# Smartboot_Prototype_version_4.net
KiCad netlist of a schematic drawn in EAGLE
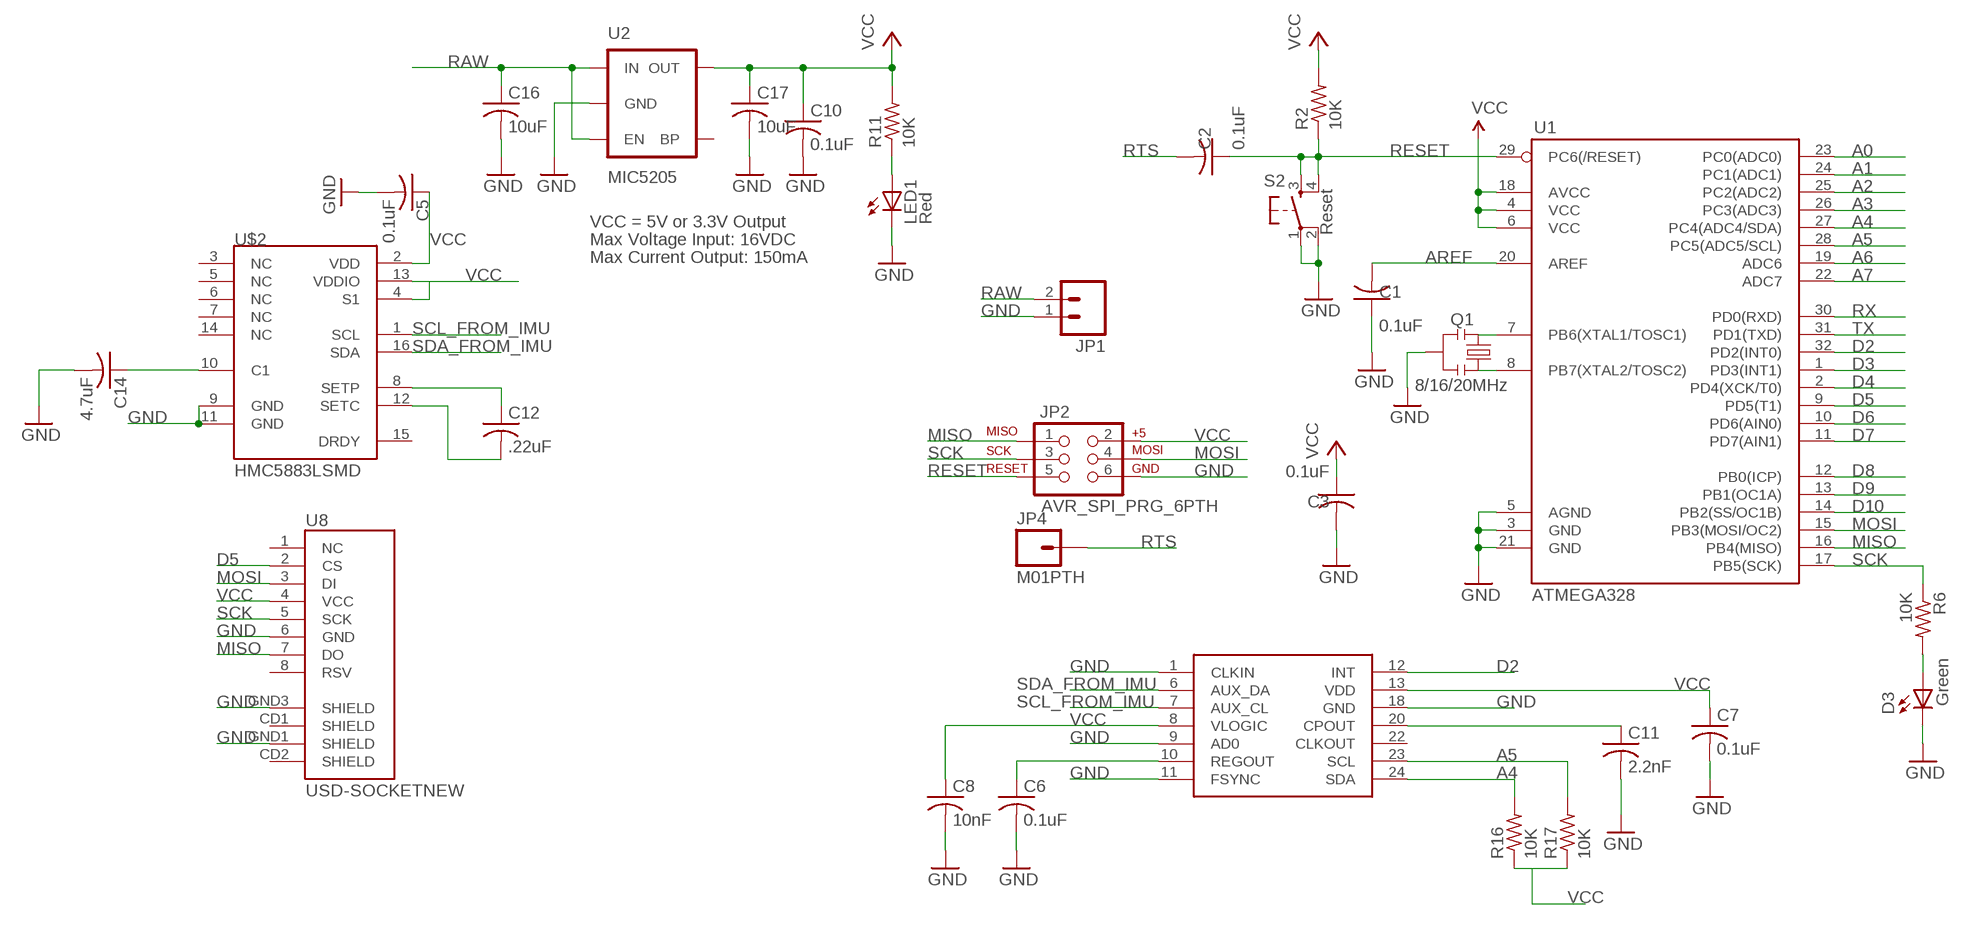
[diagram p0: schematic, sheet 1]
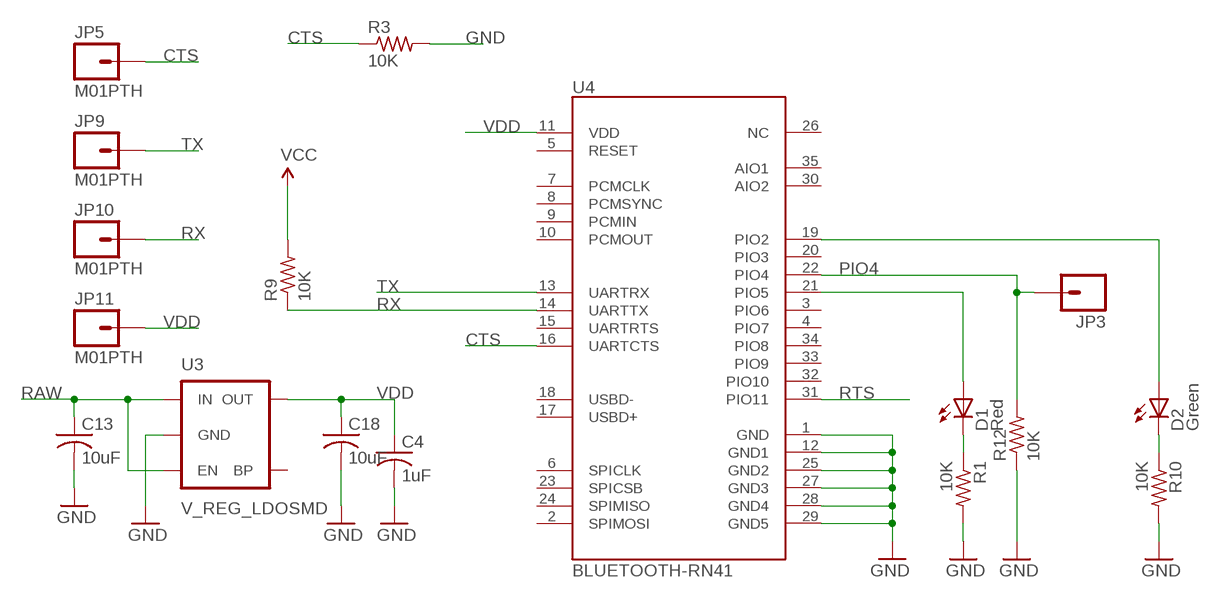
[diagram p1: schematic, sheet 2]

(export (version "E")
  (design (tool "Eeschema 10.0.6"))
  (components
    (comp (ref "C4")
      (value "1uF")
      (footprint "eagle-import:C0603")
      (libsource (lib "eagle-import") (part "C-USC0603"))
    )
    (comp (ref "C13")
      (value "10uF")
      (footprint "eagle-import:C0603")
      (libsource (lib "eagle-import") (part "C-USC0603"))
    )
    (comp (ref "C18")
      (value "10uF")
      (footprint "eagle-import:C0603")
      (libsource (lib "eagle-import") (part "C-USC0603"))
    )
    (comp (ref "D1")
      (value "Red")
      (footprint "eagle-import:LED-0603")
      (libsource (lib "eagle-import") (part "LED0603"))
    )
    (comp (ref "D2")
      (value "Green")
      (footprint "eagle-import:LED-0603")
      (libsource (lib "eagle-import") (part "LED0603"))
    )
    (comp (ref "JP3")
      (value "M01SMDNS")
      (footprint "eagle-import:1X01NS")
      (libsource (lib "eagle-import") (part "M01SMDNS"))
    )
    (comp (ref "JP5")
      (value "M01PTH")
      (footprint "eagle-import:1X01")
      (libsource (lib "eagle-import") (part "SparkFun-Connectors_M01PTH"))
    )
    (comp (ref "JP9")
      (value "M01PTH")
      (footprint "eagle-import:1X01")
      (libsource (lib "eagle-import") (part "SparkFun-Connectors_M01PTH"))
    )
    (comp (ref "JP10")
      (value "M01PTH")
      (footprint "eagle-import:1X01")
      (libsource (lib "eagle-import") (part "SparkFun-Connectors_M01PTH"))
    )
    (comp (ref "JP11")
      (value "M01PTH")
      (footprint "eagle-import:1X01")
      (libsource (lib "eagle-import") (part "SparkFun-Connectors_M01PTH"))
    )
    (comp (ref "R1")
      (value "10K")
      (footprint "eagle-import:R0603")
      (libsource (lib "eagle-import") (part "R-US_R0603"))
    )
    (comp (ref "R3")
      (value "10K")
      (footprint "eagle-import:R0603")
      (libsource (lib "eagle-import") (part "R-US_R0603"))
    )
    (comp (ref "R9")
      (value "10K")
      (footprint "eagle-import:R0603")
      (libsource (lib "eagle-import") (part "R-US_R0603"))
    )
    (comp (ref "R10")
      (value "10K")
      (footprint "eagle-import:R0603")
      (libsource (lib "eagle-import") (part "R-US_R0603"))
    )
    (comp (ref "R12")
      (value "10K")
      (footprint "eagle-import:R0603")
      (libsource (lib "eagle-import") (part "R-US_R0603"))
    )
    (comp (ref "U3")
      (value "V_REG_LDOSMD")
      (footprint "eagle-import:SOT23-5")
      (libsource (lib "eagle-import") (part "V_REG_LDOSMD"))
    )
    (comp (ref "U4")
      (value "BLUETOOTH-RN41")
      (footprint "eagle-import:RN41")
      (libsource (lib "eagle-import") (part "BLUETOOTH-RN41{dblquote}"))
    )
    (comp (ref "C1")
      (value "0.1uF")
      (footprint "eagle-import:C0603")
      (libsource (lib "eagle-import") (part "C-USC0603"))
    )
    (comp (ref "C2")
      (value "0.1uF")
      (footprint "eagle-import:C0603")
      (libsource (lib "eagle-import") (part "C-USC0603"))
    )
    (comp (ref "C3")
      (value "0.1uF")
      (footprint "eagle-import:C0603")
      (libsource (lib "eagle-import") (part "C-USC0603"))
    )
    (comp (ref "C5")
      (value "0.1uF")
      (footprint "eagle-import:C0603")
      (libsource (lib "eagle-import") (part "C-USC0603"))
    )
    (comp (ref "C6")
      (value "0.1uF")
      (footprint "eagle-import:C0603")
      (libsource (lib "eagle-import") (part "C-USC0603"))
    )
    (comp (ref "C7")
      (value "0.1uF")
      (footprint "eagle-import:C0603")
      (libsource (lib "eagle-import") (part "C-USC0603"))
    )
    (comp (ref "C8")
      (value "10nF")
      (footprint "eagle-import:C0603")
      (libsource (lib "eagle-import") (part "C-USC0603"))
    )
    (comp (ref "C10")
      (value "0.1uF")
      (footprint "eagle-import:C0603")
      (libsource (lib "eagle-import") (part "C-USC0603"))
    )
    (comp (ref "C11")
      (value "2.2nF")
      (footprint "eagle-import:C0603")
      (libsource (lib "eagle-import") (part "C-USC0603"))
    )
    (comp (ref "C12")
      (value ".22uF")
      (footprint "eagle-import:C0603")
      (libsource (lib "eagle-import") (part "C-USC0603"))
    )
    (comp (ref "C14")
      (value "4.7uF")
      (footprint "eagle-import:C0603")
      (libsource (lib "eagle-import") (part "C-USC0603"))
    )
    (comp (ref "C16")
      (value "10uF")
      (footprint "eagle-import:C0603")
      (libsource (lib "eagle-import") (part "C-USC0603"))
    )
    (comp (ref "C17")
      (value "10uF")
      (footprint "eagle-import:C0603")
      (libsource (lib "eagle-import") (part "C-USC0603"))
    )
    (comp (ref "D3")
      (value "Green")
      (footprint "eagle-import:LED-0603")
      (libsource (lib "eagle-import") (part "LED0603"))
    )
    (comp (ref "JP1")
      (value "M02-JST-2MM-SMT")
      (footprint "eagle-import:JST-2-SMD")
      (libsource (lib "eagle-import") (part "M02-JST-2MM-SMT"))
    )
    (comp (ref "JP2")
      (value "AVR_SPI_PRG_6PTH")
      (footprint "eagle-import:2X3")
      (libsource (lib "eagle-import") (part "AVR_SPI_PRG_6PTH"))
    )
    (comp (ref "JP4")
      (value "M01PTH")
      (footprint "eagle-import:1X01")
      (libsource (lib "eagle-import") (part "SparkFun-Connectors_M01PTH"))
    )
    (comp (ref "LED1")
      (value "Red")
      (footprint "eagle-import:LED-0603")
      (libsource (lib "eagle-import") (part "LED0603"))
    )
    (comp (ref "Q1")
      (value "8/16/20MHz")
      (footprint "eagle-import:RESONATOR-SMD")
      (libsource (lib "eagle-import") (part "RESONATORSMD"))
    )
    (comp (ref "R2")
      (value "10K")
      (footprint "eagle-import:R0603")
      (libsource (lib "eagle-import") (part "R-US_R0603"))
    )
    (comp (ref "R6")
      (value "10K")
      (footprint "eagle-import:R0603")
      (libsource (lib "eagle-import") (part "R-US_R0603"))
    )
    (comp (ref "R11")
      (value "10K")
      (footprint "eagle-import:R0603")
      (libsource (lib "eagle-import") (part "R-US_R0603"))
    )
    (comp (ref "R16")
      (value "10K")
      (footprint "eagle-import:R0603")
      (libsource (lib "eagle-import") (part "R-US_R0603"))
    )
    (comp (ref "R17")
      (value "10K")
      (footprint "eagle-import:R0603")
      (libsource (lib "eagle-import") (part "R-US_R0603"))
    )
    (comp (ref "S2")
      (value "Reset")
      (footprint "eagle-import:TACTILE_SWITCH_SMD")
      (libsource (lib "eagle-import") (part "TAC_SWITCHSMD"))
    )
    (comp (ref "U$2")
      (value "HMC5883LSMD")
      (footprint "eagle-import:16LPCC")
      (libsource (lib "eagle-import") (part "HMC5883LSMD"))
    )
    (comp (ref "U$5")
      (value "MPU-6050A")
      (footprint "eagle-import:QFN-24-NP")
      (libsource (lib "eagle-import") (part "MPU-6050A"))
    )
    (comp (ref "U1")
      (value "ATMEGA328")
      (footprint "eagle-import:TQFP32-08")
      (libsource (lib "eagle-import") (part "ATMEGA168"))
    )
    (comp (ref "U2")
      (value "MIC5205")
      (footprint "eagle-import:SOT23-5")
      (libsource (lib "eagle-import") (part "V_REG_LDOSMD"))
    )
    (comp (ref "U8")
      (value "USD-SOCKETNEW")
      (footprint "eagle-import:MICRO-SD-SOCKET-PP")
      (libsource (lib "eagle-import") (part "USD-SOCKETNEW"))
    )
  )
  (nets
    (net (code "1") (name "A0") (class "Default")
      (node (ref "U1") (pin "23") (pinfunction "PC0(ADC0)_23") (pintype "bidirectional"))
    )
    (net (code "2") (name "A1") (class "Default")
      (node (ref "U1") (pin "24") (pinfunction "PC1(ADC1)_24") (pintype "bidirectional"))
    )
    (net (code "3") (name "A2") (class "Default")
      (node (ref "U1") (pin "25") (pinfunction "PC2(ADC2)_25") (pintype "bidirectional"))
    )
    (net (code "4") (name "A3") (class "Default")
      (node (ref "U1") (pin "26") (pinfunction "PC3(ADC3)_26") (pintype "bidirectional"))
    )
    (net (code "5") (name "A4") (class "Default")
      (node (ref "R16") (pin "2") (pinfunction "2_2") (pintype "passive"))
      (node (ref "U$5") (pin "24") (pinfunction "SDA_24") (pintype "bidirectional"))
      (node (ref "U1") (pin "27") (pinfunction "PC4(ADC4/SDA)_27") (pintype "bidirectional"))
    )
    (net (code "6") (name "A5") (class "Default")
      (node (ref "R17") (pin "2") (pinfunction "2_2") (pintype "passive"))
      (node (ref "U$5") (pin "23") (pinfunction "SCL_23") (pintype "bidirectional"))
      (node (ref "U1") (pin "28") (pinfunction "PC5(ADC5/SCL)_28") (pintype "bidirectional"))
    )
    (net (code "7") (name "A6") (class "Default")
      (node (ref "U1") (pin "19") (pinfunction "ADC6_19") (pintype "bidirectional"))
    )
    (net (code "8") (name "A7") (class "Default")
      (node (ref "U1") (pin "22") (pinfunction "ADC7_22") (pintype "bidirectional"))
    )
    (net (code "9") (name "AREF") (class "Default")
      (node (ref "C1") (pin "2") (pinfunction "2_2") (pintype "passive"))
      (node (ref "U1") (pin "20") (pinfunction "AREF_20") (pintype "bidirectional"))
    )
    (net (code "10") (name "CTS") (class "Default")
      (node (ref "JP5") (pin "1") (pinfunction "1_1") (pintype "passive"))
      (node (ref "R3") (pin "1") (pinfunction "1_1") (pintype "passive"))
      (node (ref "U4") (pin "16") (pinfunction "UARTCTS_16") (pintype "bidirectional"))
    )
    (net (code "11") (name "D2") (class "Default")
      (node (ref "U$5") (pin "12") (pinfunction "INT_12") (pintype "bidirectional"))
      (node (ref "U1") (pin "32") (pinfunction "PD2(INT0)_32") (pintype "bidirectional"))
    )
    (net (code "12") (name "D3") (class "Default")
      (node (ref "U1") (pin "1") (pinfunction "PD3(INT1)_1") (pintype "bidirectional"))
    )
    (net (code "13") (name "D4") (class "Default")
      (node (ref "U1") (pin "2") (pinfunction "PD4(XCK/T0)_2") (pintype "bidirectional"))
    )
    (net (code "14") (name "D5") (class "Default")
      (node (ref "U1") (pin "9") (pinfunction "PD5(T1)_9") (pintype "bidirectional"))
      (node (ref "U8") (pin "2") (pinfunction "CS_2") (pintype "bidirectional"))
    )
    (net (code "15") (name "D6") (class "Default")
      (node (ref "U1") (pin "10") (pinfunction "PD6(AIN0)_10") (pintype "bidirectional"))
    )
    (net (code "16") (name "D7") (class "Default")
      (node (ref "U1") (pin "11") (pinfunction "PD7(AIN1)_11") (pintype "bidirectional"))
    )
    (net (code "17") (name "D8") (class "Default")
      (node (ref "U1") (pin "12") (pinfunction "PB0(ICP)_12") (pintype "bidirectional"))
    )
    (net (code "18") (name "D9") (class "Default")
      (node (ref "U1") (pin "13") (pinfunction "PB1(OC1A)_13") (pintype "bidirectional"))
    )
    (net (code "19") (name "D10") (class "Default")
      (node (ref "U1") (pin "14") (pinfunction "PB2(SS/OC1B)_14") (pintype "bidirectional"))
    )
    (net (code "20") (name "GND") (class "Default")
      (node (ref "C1") (pin "1") (pinfunction "1_1") (pintype "passive"))
      (node (ref "C10") (pin "2") (pinfunction "2_2") (pintype "passive"))
      (node (ref "C11") (pin "2") (pinfunction "2_2") (pintype "passive"))
      (node (ref "C13") (pin "2") (pinfunction "2_2") (pintype "passive"))
      (node (ref "C14") (pin "2") (pinfunction "2_2") (pintype "passive"))
      (node (ref "C16") (pin "2") (pinfunction "2_2") (pintype "passive"))
      (node (ref "C17") (pin "2") (pinfunction "2_2") (pintype "passive"))
      (node (ref "C18") (pin "2") (pinfunction "2_2") (pintype "passive"))
      (node (ref "C3") (pin "2") (pinfunction "2_2") (pintype "passive"))
      (node (ref "C4") (pin "2") (pinfunction "2_2") (pintype "passive"))
      (node (ref "C5") (pin "2") (pinfunction "2_2") (pintype "passive"))
      (node (ref "C6") (pin "2") (pinfunction "2_2") (pintype "passive"))
      (node (ref "C7") (pin "2") (pinfunction "2_2") (pintype "passive"))
      (node (ref "C8") (pin "2") (pinfunction "2_2") (pintype "passive"))
      (node (ref "D3") (pin "C") (pinfunction "C_C") (pintype "passive"))
      (node (ref "JP1") (pin "1") (pinfunction "2_1") (pintype "passive"))
      (node (ref "JP2") (pin "6") (pinfunction "6_6") (pintype "passive"))
      (node (ref "LED1") (pin "C") (pinfunction "C_C") (pintype "passive"))
      (node (ref "Q1") (pin "2") (pinfunction "2_2") (pintype "passive"))
      (node (ref "R1") (pin "2") (pinfunction "2_2") (pintype "passive"))
      (node (ref "R10") (pin "2") (pinfunction "2_2") (pintype "passive"))
      (node (ref "R12") (pin "1") (pinfunction "1_1") (pintype "passive"))
      (node (ref "R3") (pin "2") (pinfunction "2_2") (pintype "passive"))
      (node (ref "S2") (pin "1") (pinfunction "1_1") (pintype "passive"))
      (node (ref "S2") (pin "2") (pinfunction "2_2") (pintype "passive"))
      (node (ref "U$2") (pin "11") (pinfunction "GND_11") (pintype "bidirectional"))
      (node (ref "U$2") (pin "9") (pinfunction "GND_9") (pintype "bidirectional"))
      (node (ref "U$5") (pin "1") (pinfunction "CLKIN_1") (pintype "bidirectional"))
      (node (ref "U$5") (pin "11") (pinfunction "FSYNC_11") (pintype "bidirectional"))
      (node (ref "U$5") (pin "18") (pinfunction "GND_18") (pintype "bidirectional"))
      (node (ref "U$5") (pin "9") (pinfunction "AD0_9") (pintype "bidirectional"))
      (node (ref "U1") (pin "21") (pinfunction "GND_21") (pintype "bidirectional"))
      (node (ref "U1") (pin "3") (pinfunction "GND_3") (pintype "bidirectional"))
      (node (ref "U1") (pin "5") (pinfunction "AGND_5") (pintype "bidirectional"))
      (node (ref "U2") (pin "2") (pinfunction "GND_2") (pintype "input"))
      (node (ref "U3") (pin "2") (pinfunction "GND_2") (pintype "input"))
      (node (ref "U4") (pin "1") (pinfunction "GND_1") (pintype "bidirectional"))
      (node (ref "U4") (pin "12") (pinfunction "GND1_12") (pintype "bidirectional"))
      (node (ref "U4") (pin "25") (pinfunction "GND2_25") (pintype "bidirectional"))
      (node (ref "U4") (pin "27") (pinfunction "GND3_27") (pintype "bidirectional"))
      (node (ref "U4") (pin "28") (pinfunction "GND4_28") (pintype "bidirectional"))
      (node (ref "U4") (pin "29") (pinfunction "GND5_29") (pintype "bidirectional"))
      (node (ref "U8") (pin "6") (pinfunction "GND_6") (pintype "bidirectional"))
      (node (ref "U8") (pin "GND1") (pinfunction "SHIELD_GND1") (pintype "bidirectional"))
      (node (ref "U8") (pin "GND3") (pinfunction "SHIELD_GND3") (pintype "bidirectional"))
    )
    (net (code "21") (name "MISO") (class "Default")
      (node (ref "JP2") (pin "1") (pinfunction "1_1") (pintype "passive"))
      (node (ref "U1") (pin "16") (pinfunction "PB4(MISO)_16") (pintype "bidirectional"))
      (node (ref "U8") (pin "7") (pinfunction "DO_7") (pintype "bidirectional"))
    )
    (net (code "22") (name "MOSI") (class "Default")
      (node (ref "JP2") (pin "4") (pinfunction "4_4") (pintype "passive"))
      (node (ref "U1") (pin "15") (pinfunction "PB3(MOSI/OC2)_15") (pintype "bidirectional"))
      (node (ref "U8") (pin "3") (pinfunction "DI_3") (pintype "bidirectional"))
    )
    (net (code "23") (name "Net-(D1-PadC)") (class "Default")
      (node (ref "D1") (pin "C") (pinfunction "C_C") (pintype "passive"))
      (node (ref "R1") (pin "1") (pinfunction "1_1") (pintype "passive"))
    )
    (net (code "24") (name "Net-(D2-PadC)") (class "Default")
      (node (ref "D2") (pin "C") (pinfunction "C_C") (pintype "passive"))
      (node (ref "R10") (pin "1") (pinfunction "1_1") (pintype "passive"))
    )
    (net (code "25") (name "Net-(D3-PadA)") (class "Default")
      (node (ref "D3") (pin "A") (pinfunction "A_A") (pintype "passive"))
      (node (ref "R6") (pin "2") (pinfunction "2_2") (pintype "passive"))
    )
    (net (code "26") (name "Net-(LED1-PadA)") (class "Default")
      (node (ref "LED1") (pin "A") (pinfunction "A_A") (pintype "passive"))
      (node (ref "R11") (pin "1") (pinfunction "1_1") (pintype "passive"))
    )
    (net (code "27") (name "Net-(U$2-C1)") (class "Default")
      (node (ref "C14") (pin "1") (pinfunction "1_1") (pintype "passive"))
      (node (ref "U$2") (pin "10") (pinfunction "C1_10") (pintype "bidirectional"))
    )
    (net (code "28") (name "Net-(U$2-SETC)") (class "Default")
      (node (ref "C12") (pin "2") (pinfunction "2_2") (pintype "passive"))
      (node (ref "U$2") (pin "12") (pinfunction "SETC_12") (pintype "bidirectional"))
    )
    (net (code "29") (name "Net-(U$2-SETP)") (class "Default")
      (node (ref "C12") (pin "1") (pinfunction "1_1") (pintype "passive"))
      (node (ref "U$2") (pin "8") (pinfunction "SETP_8") (pintype "bidirectional"))
    )
    (net (code "30") (name "Net-(U$5-CPOUT)") (class "Default")
      (node (ref "C11") (pin "1") (pinfunction "1_1") (pintype "passive"))
      (node (ref "U$5") (pin "20") (pinfunction "CPOUT_20") (pintype "bidirectional"))
    )
    (net (code "31") (name "Net-(U$5-REGOUT)") (class "Default")
      (node (ref "C6") (pin "1") (pinfunction "1_1") (pintype "passive"))
      (node (ref "U$5") (pin "10") (pinfunction "REGOUT_10") (pintype "bidirectional"))
    )
    (net (code "32") (name "Net-(U1-PB6(XTAL1{slash}TOSC1))") (class "Default")
      (node (ref "Q1") (pin "3") (pinfunction "3_3") (pintype "passive"))
      (node (ref "U1") (pin "7") (pinfunction "PB6(XTAL1/TOSC1)_7") (pintype "bidirectional"))
    )
    (net (code "33") (name "Net-(U1-PB7(XTAL2{slash}TOSC2))") (class "Default")
      (node (ref "Q1") (pin "1") (pinfunction "1_1") (pintype "passive"))
      (node (ref "U1") (pin "8") (pinfunction "PB7(XTAL2/TOSC2)_8") (pintype "bidirectional"))
    )
    (net (code "34") (name "Net-(U4-PIO2)") (class "Default")
      (node (ref "D2") (pin "A") (pinfunction "A_A") (pintype "passive"))
      (node (ref "U4") (pin "19") (pinfunction "PIO2_19") (pintype "bidirectional"))
    )
    (net (code "35") (name "Net-(U4-PIO5)") (class "Default")
      (node (ref "D1") (pin "A") (pinfunction "A_A") (pintype "passive"))
      (node (ref "U4") (pin "21") (pinfunction "PIO5_21") (pintype "bidirectional"))
    )
    (net (code "36") (name "PIO4") (class "Default")
      (node (ref "JP3") (pin "1") (pinfunction "1_1") (pintype "passive"))
      (node (ref "R12") (pin "2") (pinfunction "2_2") (pintype "passive"))
      (node (ref "U4") (pin "22") (pinfunction "PIO4_22") (pintype "bidirectional"))
    )
    (net (code "37") (name "RAW") (class "Default")
      (node (ref "C13") (pin "1") (pinfunction "1_1") (pintype "passive"))
      (node (ref "C16") (pin "1") (pinfunction "1_1") (pintype "passive"))
      (node (ref "JP1") (pin "2") (pinfunction "1_2") (pintype "passive"))
      (node (ref "U2") (pin "1") (pinfunction "IN_1") (pintype "input"))
      (node (ref "U2") (pin "3") (pinfunction "EN_3") (pintype "input"))
      (node (ref "U3") (pin "1") (pinfunction "IN_1") (pintype "input"))
      (node (ref "U3") (pin "3") (pinfunction "EN_3") (pintype "input"))
    )
    (net (code "38") (name "RESET") (class "Default")
      (node (ref "C2") (pin "1") (pinfunction "1_1") (pintype "passive"))
      (node (ref "JP2") (pin "5") (pinfunction "5_5") (pintype "passive"))
      (node (ref "R2") (pin "1") (pinfunction "1_1") (pintype "passive"))
      (node (ref "S2") (pin "3") (pinfunction "3_3") (pintype "passive"))
      (node (ref "S2") (pin "4") (pinfunction "4_4") (pintype "passive"))
      (node (ref "U1") (pin "29") (pinfunction "PC6(/RESET)_29") (pintype "bidirectional"))
    )
    (net (code "39") (name "RTS") (class "Default")
      (node (ref "C2") (pin "2") (pinfunction "2_2") (pintype "passive"))
      (node (ref "JP4") (pin "1") (pinfunction "1_1") (pintype "passive"))
      (node (ref "U4") (pin "31") (pinfunction "PIO11_31") (pintype "bidirectional"))
    )
    (net (code "40") (name "RX") (class "Default")
      (node (ref "JP10") (pin "1") (pinfunction "1_1") (pintype "passive"))
      (node (ref "R9") (pin "1") (pinfunction "1_1") (pintype "passive"))
      (node (ref "U1") (pin "30") (pinfunction "PD0(RXD)_30") (pintype "bidirectional"))
      (node (ref "U4") (pin "14") (pinfunction "UARTTX_14") (pintype "bidirectional"))
    )
    (net (code "41") (name "SCK") (class "Default")
      (node (ref "JP2") (pin "3") (pinfunction "3_3") (pintype "passive"))
      (node (ref "R6") (pin "1") (pinfunction "1_1") (pintype "passive"))
      (node (ref "U1") (pin "17") (pinfunction "PB5(SCK)_17") (pintype "bidirectional"))
      (node (ref "U8") (pin "5") (pinfunction "SCK_5") (pintype "bidirectional"))
    )
    (net (code "42") (name "SCL_FROM_IMU") (class "Default")
      (node (ref "U$2") (pin "1") (pinfunction "SCL_1") (pintype "bidirectional"))
      (node (ref "U$5") (pin "7") (pinfunction "AUX_CL_7") (pintype "bidirectional"))
    )
    (net (code "43") (name "SDA_FROM_IMU") (class "Default")
      (node (ref "U$2") (pin "16") (pinfunction "SDA_16") (pintype "bidirectional"))
      (node (ref "U$5") (pin "6") (pinfunction "AUX_DA_6") (pintype "bidirectional"))
    )
    (net (code "44") (name "TX") (class "Default")
      (node (ref "JP9") (pin "1") (pinfunction "1_1") (pintype "passive"))
      (node (ref "U1") (pin "31") (pinfunction "PD1(TXD)_31") (pintype "bidirectional"))
      (node (ref "U4") (pin "13") (pinfunction "UARTRX_13") (pintype "bidirectional"))
    )
    (net (code "45") (name "VCC") (class "Default")
      (node (ref "C10") (pin "1") (pinfunction "1_1") (pintype "passive"))
      (node (ref "C17") (pin "1") (pinfunction "1_1") (pintype "passive"))
      (node (ref "C3") (pin "1") (pinfunction "1_1") (pintype "passive"))
      (node (ref "C5") (pin "1") (pinfunction "1_1") (pintype "passive"))
      (node (ref "C7") (pin "1") (pinfunction "1_1") (pintype "passive"))
      (node (ref "C8") (pin "1") (pinfunction "1_1") (pintype "passive"))
      (node (ref "JP2") (pin "2") (pinfunction "2_2") (pintype "passive"))
      (node (ref "R11") (pin "2") (pinfunction "2_2") (pintype "passive"))
      (node (ref "R16") (pin "1") (pinfunction "1_1") (pintype "passive"))
      (node (ref "R17") (pin "1") (pinfunction "1_1") (pintype "passive"))
      (node (ref "R2") (pin "2") (pinfunction "2_2") (pintype "passive"))
      (node (ref "R9") (pin "2") (pinfunction "2_2") (pintype "passive"))
      (node (ref "U$2") (pin "13") (pinfunction "VDDIO_13") (pintype "bidirectional"))
      (node (ref "U$2") (pin "2") (pinfunction "VDD_2") (pintype "bidirectional"))
      (node (ref "U$2") (pin "4") (pinfunction "S1_4") (pintype "bidirectional"))
      (node (ref "U$5") (pin "13") (pinfunction "VDD_13") (pintype "bidirectional"))
      (node (ref "U$5") (pin "8") (pinfunction "VLOGIC_8") (pintype "bidirectional"))
      (node (ref "U1") (pin "18") (pinfunction "AVCC_18") (pintype "bidirectional"))
      (node (ref "U1") (pin "4") (pinfunction "VCC_4") (pintype "bidirectional"))
      (node (ref "U1") (pin "6") (pinfunction "VCC_6") (pintype "bidirectional"))
      (node (ref "U2") (pin "5") (pinfunction "OUT_5") (pintype "passive"))
      (node (ref "U8") (pin "4") (pinfunction "VCC_4") (pintype "bidirectional"))
    )
    (net (code "46") (name "VDD") (class "Default")
      (node (ref "C18") (pin "1") (pinfunction "1_1") (pintype "passive"))
      (node (ref "C4") (pin "1") (pinfunction "1_1") (pintype "passive"))
      (node (ref "JP11") (pin "1") (pinfunction "1_1") (pintype "passive"))
      (node (ref "U3") (pin "5") (pinfunction "OUT_5") (pintype "passive"))
      (node (ref "U4") (pin "11") (pinfunction "VDD_11") (pintype "bidirectional"))
    )
    (net (code "47") (name "unconnected-(U$2-DRDY-Pad15)") (class "Default")
      (node (ref "U$2") (pin "15") (pinfunction "DRDY_15") (pintype "bidirectional"))
    )
    (net (code "48") (name "unconnected-(U$2-NC-Pad3)") (class "Default")
      (node (ref "U$2") (pin "3") (pinfunction "NC_3") (pintype "bidirectional"))
    )
    (net (code "49") (name "unconnected-(U$2-NC-Pad5)") (class "Default")
      (node (ref "U$2") (pin "5") (pinfunction "NC_5") (pintype "bidirectional"))
    )
    (net (code "50") (name "unconnected-(U$2-NC-Pad6)") (class "Default")
      (node (ref "U$2") (pin "6") (pinfunction "NC_6") (pintype "bidirectional"))
    )
    (net (code "51") (name "unconnected-(U$2-NC-Pad7)") (class "Default")
      (node (ref "U$2") (pin "7") (pinfunction "NC_7") (pintype "bidirectional"))
    )
    (net (code "52") (name "unconnected-(U$2-NC-Pad14)") (class "Default")
      (node (ref "U$2") (pin "14") (pinfunction "NC_14") (pintype "bidirectional"))
    )
    (net (code "53") (name "unconnected-(U$5-CLKOUT-Pad22)") (class "Default")
      (node (ref "U$5") (pin "22") (pinfunction "CLKOUT_22") (pintype "bidirectional"))
    )
    (net (code "54") (name "unconnected-(U2-BP-Pad4)") (class "Default")
      (node (ref "U2") (pin "4") (pinfunction "BP_4") (pintype "input"))
    )
    (net (code "55") (name "unconnected-(U3-BP-Pad4)") (class "Default")
      (node (ref "U3") (pin "4") (pinfunction "BP_4") (pintype "input"))
    )
    (net (code "56") (name "unconnected-(U4-AIO1-Pad35)") (class "Default")
      (node (ref "U4") (pin "35") (pinfunction "AIO1_35") (pintype "bidirectional"))
    )
    (net (code "57") (name "unconnected-(U4-AIO2-Pad30)") (class "Default")
      (node (ref "U4") (pin "30") (pinfunction "AIO2_30") (pintype "bidirectional"))
    )
    (net (code "58") (name "unconnected-(U4-NC-Pad26)") (class "Default")
      (node (ref "U4") (pin "26") (pinfunction "NC_26") (pintype "bidirectional"))
    )
    (net (code "59") (name "unconnected-(U4-PCMCLK-Pad7)") (class "Default")
      (node (ref "U4") (pin "7") (pinfunction "PCMCLK_7") (pintype "bidirectional"))
    )
    (net (code "60") (name "unconnected-(U4-PCMIN-Pad9)") (class "Default")
      (node (ref "U4") (pin "9") (pinfunction "PCMIN_9") (pintype "bidirectional"))
    )
    (net (code "61") (name "unconnected-(U4-PCMOUT-Pad10)") (class "Default")
      (node (ref "U4") (pin "10") (pinfunction "PCMOUT_10") (pintype "bidirectional"))
    )
    (net (code "62") (name "unconnected-(U4-PCMSYNC-Pad8)") (class "Default")
      (node (ref "U4") (pin "8") (pinfunction "PCMSYNC_8") (pintype "bidirectional"))
    )
    (net (code "63") (name "unconnected-(U4-PIO3-Pad20)") (class "Default")
      (node (ref "U4") (pin "20") (pinfunction "PIO3_20") (pintype "bidirectional"))
    )
    (net (code "64") (name "unconnected-(U4-PIO6-Pad3)") (class "Default")
      (node (ref "U4") (pin "3") (pinfunction "PIO6_3") (pintype "bidirectional"))
    )
    (net (code "65") (name "unconnected-(U4-PIO7-Pad4)") (class "Default")
      (node (ref "U4") (pin "4") (pinfunction "PIO7_4") (pintype "bidirectional"))
    )
    (net (code "66") (name "unconnected-(U4-PIO8-Pad34)") (class "Default")
      (node (ref "U4") (pin "34") (pinfunction "PIO8_34") (pintype "bidirectional"))
    )
    (net (code "67") (name "unconnected-(U4-PIO9-Pad33)") (class "Default")
      (node (ref "U4") (pin "33") (pinfunction "PIO9_33") (pintype "bidirectional"))
    )
    (net (code "68") (name "unconnected-(U4-PIO10-Pad32)") (class "Default")
      (node (ref "U4") (pin "32") (pinfunction "PIO10_32") (pintype "bidirectional"))
    )
    (net (code "69") (name "unconnected-(U4-RESET-Pad5)") (class "Default")
      (node (ref "U4") (pin "5") (pinfunction "RESET_5") (pintype "bidirectional"))
    )
    (net (code "70") (name "unconnected-(U4-SPICLK-Pad6)") (class "Default")
      (node (ref "U4") (pin "6") (pinfunction "SPICLK_6") (pintype "bidirectional"))
    )
    (net (code "71") (name "unconnected-(U4-SPICSB-Pad23)") (class "Default")
      (node (ref "U4") (pin "23") (pinfunction "SPICSB_23") (pintype "bidirectional"))
    )
    (net (code "72") (name "unconnected-(U4-SPIMISO-Pad24)") (class "Default")
      (node (ref "U4") (pin "24") (pinfunction "SPIMISO_24") (pintype "bidirectional"))
    )
    (net (code "73") (name "unconnected-(U4-SPIMOSI-Pad2)") (class "Default")
      (node (ref "U4") (pin "2") (pinfunction "SPIMOSI_2") (pintype "bidirectional"))
    )
    (net (code "74") (name "unconnected-(U4-UARTRTS-Pad15)") (class "Default")
      (node (ref "U4") (pin "15") (pinfunction "UARTRTS_15") (pintype "bidirectional"))
    )
    (net (code "75") (name "unconnected-(U4-USBD+-Pad17)") (class "Default")
      (node (ref "U4") (pin "17") (pinfunction "USBD+_17") (pintype "bidirectional"))
    )
    (net (code "76") (name "unconnected-(U4-USBD--Pad18)") (class "Default")
      (node (ref "U4") (pin "18") (pinfunction "USBD-_18") (pintype "bidirectional"))
    )
    (net (code "77") (name "unconnected-(U8-NC-Pad1)") (class "Default")
      (node (ref "U8") (pin "1") (pinfunction "NC_1") (pintype "bidirectional"))
    )
    (net (code "78") (name "unconnected-(U8-RSV-Pad8)") (class "Default")
      (node (ref "U8") (pin "8") (pinfunction "RSV_8") (pintype "bidirectional"))
    )
    (net (code "79") (name "unconnected-(U8-SHIELD-PadCD1)") (class "Default")
      (node (ref "U8") (pin "CD1") (pinfunction "SHIELD_CD1") (pintype "bidirectional"))
    )
    (net (code "80") (name "unconnected-(U8-SHIELD-PadCD2)") (class "Default")
      (node (ref "U8") (pin "CD2") (pinfunction "SHIELD_CD2") (pintype "bidirectional"))
    )
  )
)
